# Gator_Environment.net
KiCad netlist of a schematic drawn in EAGLE
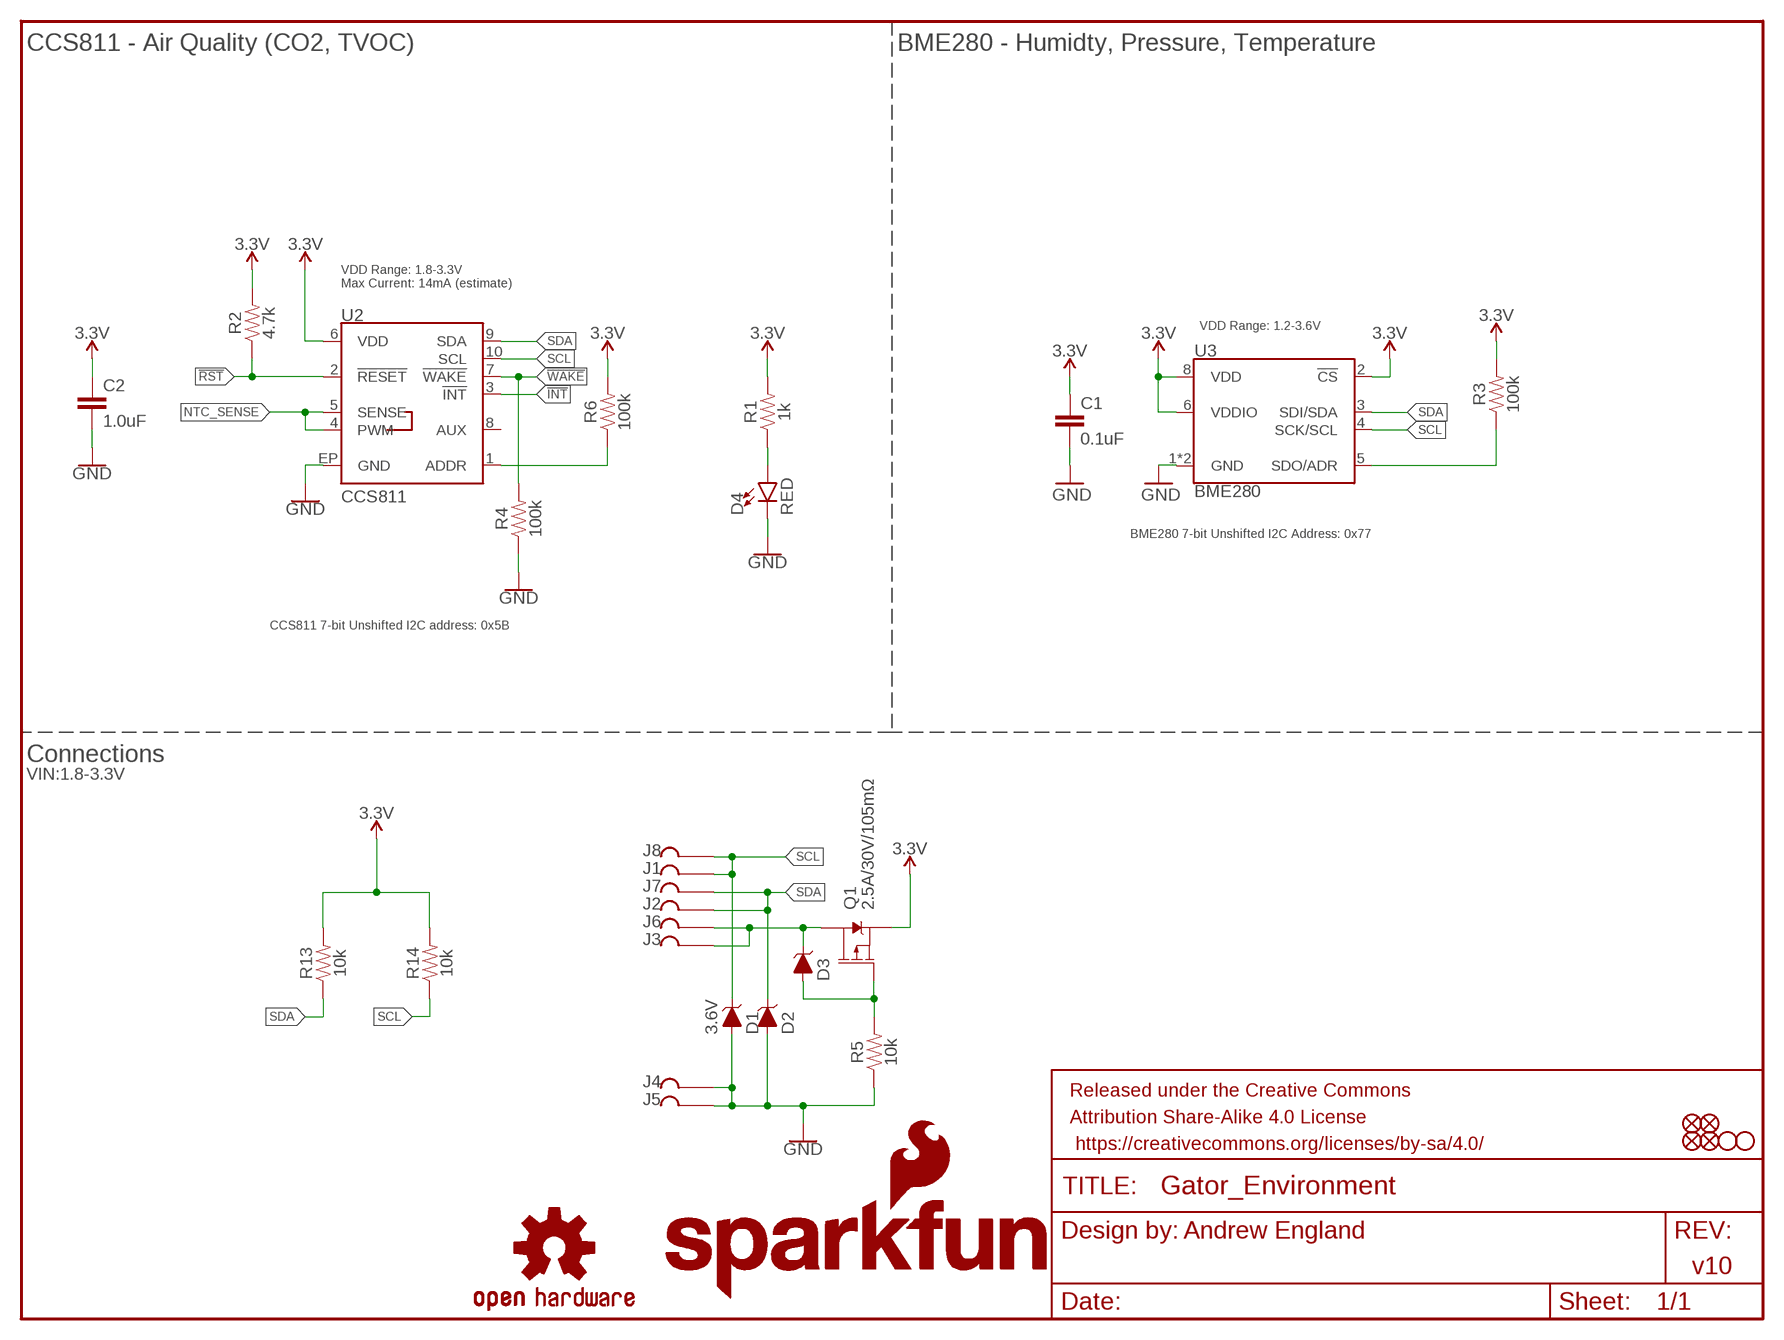
[diagram p0: schematic, sheet 1]

(export (version "E")
  (design (tool "Eeschema 10.0.6"))
  (components
    (comp (ref "C1")
      (value "0.1uF")
      (footprint "eagle-import:0603")
      (libsource (lib "eagle-import") (part "0.1UF-0603-25V-(+80/-20%)"))
    )
    (comp (ref "C2")
      (value "1.0uF")
      (footprint "eagle-import:0603")
      (libsource (lib "eagle-import") (part "1.0UF-0603-16V-10%"))
    )
    (comp (ref "D1")
      (value "3.6V")
      (footprint "eagle-import:SOD-323")
      (libsource (lib "eagle-import") (part "DIODE-ZENER-BZT52C3V6S"))
    )
    (comp (ref "D2")
      (value "3.6V")
      (footprint "eagle-import:SOD-323")
      (libsource (lib "eagle-import") (part "DIODE-ZENER-BZT52C3V6S"))
    )
    (comp (ref "D3")
      (value "3.6V")
      (footprint "eagle-import:SOD-323")
      (libsource (lib "eagle-import") (part "DIODE-ZENER-BZT52C3V6S"))
    )
    (comp (ref "D4")
      (value "RED")
      (footprint "eagle-import:LED-0603")
      (libsource (lib "eagle-import") (part "LED-RED0603"))
    )
    (comp (ref "FD1")
      (value "FIDUCIAL1X2")
      (footprint "eagle-import:FIDUCIAL-1X2")
      (libsource (lib "eagle-import") (part "FIDUCIAL1X2"))
    )
    (comp (ref "FD2")
      (value "FIDUCIAL1X2")
      (footprint "eagle-import:FIDUCIAL-1X2")
      (libsource (lib "eagle-import") (part "FIDUCIAL1X2"))
    )
    (comp (ref "FD3")
      (value "FIDUCIAL1X2")
      (footprint "eagle-import:FIDUCIAL-1X2")
      (libsource (lib "eagle-import") (part "FIDUCIAL1X2"))
    )
    (comp (ref "FD4")
      (value "FIDUCIAL1X2")
      (footprint "eagle-import:FIDUCIAL-1X2")
      (libsource (lib "eagle-import") (part "FIDUCIAL1X2"))
    )
    (comp (ref "FRAME1")
      (value "FRAME-LETTER")
      (footprint "eagle-import:CREATIVE_COMMONS")
      (libsource (lib "eagle-import") (part "FRAME-LETTER"))
    )
    (comp (ref "H2")
      (value "STAND-OFF")
      (footprint "eagle-import:STAND-OFF")
      (libsource (lib "eagle-import") (part "STAND-OFF"))
    )
    (comp (ref "H4")
      (value "STAND-OFF")
      (footprint "eagle-import:STAND-OFF")
      (libsource (lib "eagle-import") (part "STAND-OFF"))
    )
    (comp (ref "J1")
      (value "GATORGATOR_MINI")
      (footprint "eagle-import:GATOR_MINI")
      (libsource (lib "eagle-import") (part "GATORGATOR_MINI"))
    )
    (comp (ref "J2")
      (value "GATORGATOR_MINI")
      (footprint "eagle-import:GATOR_MINI")
      (libsource (lib "eagle-import") (part "GATORGATOR_MINI"))
    )
    (comp (ref "J3")
      (value "GATORGATOR_MINI")
      (footprint "eagle-import:GATOR_MINI")
      (libsource (lib "eagle-import") (part "GATORGATOR_MINI"))
    )
    (comp (ref "J4")
      (value "GATORGATOR_MINI")
      (footprint "eagle-import:GATOR_MINI")
      (libsource (lib "eagle-import") (part "GATORGATOR_MINI"))
    )
    (comp (ref "J5")
      (value "GATORGATOR_MINI")
      (footprint "eagle-import:GATOR_MINI")
      (libsource (lib "eagle-import") (part "GATORGATOR_MINI"))
    )
    (comp (ref "J6")
      (value "GATORGATOR_MINI")
      (footprint "eagle-import:GATOR_MINI")
      (libsource (lib "eagle-import") (part "GATORGATOR_MINI"))
    )
    (comp (ref "J7")
      (value "GATORGATOR_MINI")
      (footprint "eagle-import:GATOR_MINI")
      (libsource (lib "eagle-import") (part "GATORGATOR_MINI"))
    )
    (comp (ref "J8")
      (value "GATORGATOR_MINI")
      (footprint "eagle-import:GATOR_MINI")
      (libsource (lib "eagle-import") (part "GATORGATOR_MINI"))
    )
    (comp (ref "LOGO1")
      (value "SFE_LOGO_NAME.1_INCH")
      (footprint "eagle-import:SFE_LOGO_NAME_.1")
      (libsource (lib "eagle-import") (part "SFE_LOGO_NAME.1_INCH"))
    )
    (comp (ref "LOGO2")
      (value "SFE_LOGO_NAME_FLAME.1_INCH")
      (footprint "eagle-import:SFE_LOGO_NAME_FLAME_.1")
      (libsource (lib "eagle-import") (part "SFE_LOGO_NAME_FLAME.1_INCH"))
    )
    (comp (ref "LOGO4")
      (value "OSHW-LOGOS")
      (footprint "eagle-import:OSHW-LOGO-S")
      (libsource (lib "eagle-import") (part "OSHW-LOGOS"))
    )
    (comp (ref "Q1")
      (value "2.5A/30V/105mΩ")
      (footprint "eagle-import:SOT23-3")
      (libsource (lib "eagle-import") (part "MOSFET_PCH-DMG2307L"))
    )
    (comp (ref "R1")
      (value "1k")
      (footprint "eagle-import:0603")
      (libsource (lib "eagle-import") (part "1KOHM-0603-1/10W-1%"))
    )
    (comp (ref "R2")
      (value "4.7k")
      (footprint "eagle-import:0603")
      (libsource (lib "eagle-import") (part "4.7KOHM-0603-1/10W-1%"))
    )
    (comp (ref "R3")
      (value "100k")
      (footprint "eagle-import:0603")
      (libsource (lib "eagle-import") (part "100KOHM-0603-1/10W-1%"))
    )
    (comp (ref "R4")
      (value "100k")
      (footprint "eagle-import:0603")
      (libsource (lib "eagle-import") (part "100KOHM-0603-1/10W-1%"))
    )
    (comp (ref "R5")
      (value "10k")
      (footprint "eagle-import:0603")
      (libsource (lib "eagle-import") (part "10KOHM-0603-1/10W-1%"))
    )
    (comp (ref "R6")
      (value "100k")
      (footprint "eagle-import:0603")
      (libsource (lib "eagle-import") (part "100KOHM-0603-1/10W-1%"))
    )
    (comp (ref "R13")
      (value "10k")
      (footprint "eagle-import:0603")
      (libsource (lib "eagle-import") (part "10KOHM-0603-1/10W-1%"))
    )
    (comp (ref "R14")
      (value "10k")
      (footprint "eagle-import:0603")
      (libsource (lib "eagle-import") (part "10KOHM-0603-1/10W-1%"))
    )
    (comp (ref "U2")
      (value "CCS811")
      (footprint "eagle-import:LGA10")
      (libsource (lib "eagle-import") (part "CCS811PRODUCTION"))
    )
    (comp (ref "U3")
      (value "BME280")
      (footprint "eagle-import:LGA-8-2.5X2.5")
      (libsource (lib "eagle-import") (part "BME280"))
    )
  )
  (nets
    (net (code "1") (name "/~{INT}") (class "Default")
      (node (ref "U2") (pin "3") (pinfunction "~{INT}_3") (pintype "bidirectional"))
    )
    (net (code "2") (name "/~{RST}") (class "Default")
      (node (ref "R2") (pin "1") (pinfunction "1_1") (pintype "passive"))
      (node (ref "U2") (pin "2") (pinfunction "~{RESET}_2") (pintype "bidirectional"))
    )
    (net (code "3") (name "/~{WAKE}") (class "Default")
      (node (ref "R4") (pin "2") (pinfunction "2_2") (pintype "passive"))
      (node (ref "U2") (pin "7") (pinfunction "~{WAKE}_7") (pintype "bidirectional"))
    )
    (net (code "4") (name "3.3V") (class "Default")
      (node (ref "C1") (pin "1") (pinfunction "1_1") (pintype "passive"))
      (node (ref "C2") (pin "1") (pinfunction "1_1") (pintype "passive"))
      (node (ref "Q1") (pin "2") (pinfunction "S_2") (pintype "bidirectional"))
      (node (ref "R1") (pin "2") (pinfunction "2_2") (pintype "passive"))
      (node (ref "R13") (pin "2") (pinfunction "2_2") (pintype "passive"))
      (node (ref "R14") (pin "2") (pinfunction "2_2") (pintype "passive"))
      (node (ref "R2") (pin "2") (pinfunction "2_2") (pintype "passive"))
      (node (ref "R3") (pin "2") (pinfunction "2_2") (pintype "passive"))
      (node (ref "R6") (pin "2") (pinfunction "2_2") (pintype "passive"))
      (node (ref "U2") (pin "6") (pinfunction "VDD_6") (pintype "bidirectional"))
      (node (ref "U3") (pin "2") (pinfunction "~{CS}_2") (pintype "bidirectional"))
      (node (ref "U3") (pin "6") (pinfunction "VDDIO_6") (pintype "bidirectional"))
      (node (ref "U3") (pin "8") (pinfunction "VDD_8") (pintype "bidirectional"))
    )
    (net (code "5") (name "GND") (class "Default")
      (node (ref "C1") (pin "2") (pinfunction "2_2") (pintype "passive"))
      (node (ref "C2") (pin "2") (pinfunction "2_2") (pintype "passive"))
      (node (ref "D1") (pin "A") (pinfunction "A_A") (pintype "passive"))
      (node (ref "D2") (pin "A") (pinfunction "A_A") (pintype "passive"))
      (node (ref "D4") (pin "C") (pinfunction "C_C") (pintype "passive"))
      (node (ref "J4") (pin "P$2") (pinfunction "P$1_P$2") (pintype "bidirectional"))
      (node (ref "J5") (pin "P$2") (pinfunction "P$1_P$2") (pintype "bidirectional"))
      (node (ref "R4") (pin "1") (pinfunction "1_1") (pintype "passive"))
      (node (ref "R5") (pin "1") (pinfunction "1_1") (pintype "passive"))
      (node (ref "U2") (pin "EP") (pinfunction "GND_EP") (pintype "bidirectional"))
      (node (ref "U3") (pin "1") (pinfunction "GND_1") (pintype "bidirectional"))
      (node (ref "U3") (pin "7") (pinfunction "GND_7") (pintype "bidirectional"))
    )
    (net (code "6") (name "NTC_SENSE") (class "Default")
      (node (ref "U2") (pin "4") (pinfunction "PWM_4") (pintype "bidirectional"))
      (node (ref "U2") (pin "5") (pinfunction "SENSE_5") (pintype "bidirectional"))
    )
    (net (code "7") (name "Net-(D4-PadA)") (class "Default")
      (node (ref "D4") (pin "A") (pinfunction "A_A") (pintype "passive"))
      (node (ref "R1") (pin "1") (pinfunction "1_1") (pintype "passive"))
    )
    (net (code "8") (name "Net-(J3-P$1)") (class "Default")
      (node (ref "D3") (pin "C") (pinfunction "C_C") (pintype "passive"))
      (node (ref "J3") (pin "P$2") (pinfunction "P$1_P$2") (pintype "bidirectional"))
      (node (ref "J6") (pin "P$2") (pinfunction "P$1_P$2") (pintype "bidirectional"))
      (node (ref "Q1") (pin "3") (pinfunction "D_3") (pintype "bidirectional"))
    )
    (net (code "9") (name "Net-(Q1-G)") (class "Default")
      (node (ref "D3") (pin "A") (pinfunction "A_A") (pintype "passive"))
      (node (ref "Q1") (pin "1") (pinfunction "G_1") (pintype "bidirectional"))
      (node (ref "R5") (pin "2") (pinfunction "2_2") (pintype "passive"))
    )
    (net (code "10") (name "Net-(U2-ADDR)") (class "Default")
      (node (ref "R6") (pin "1") (pinfunction "1_1") (pintype "passive"))
      (node (ref "U2") (pin "1") (pinfunction "ADDR_1") (pintype "bidirectional"))
    )
    (net (code "11") (name "Net-(U3-SDO{slash}ADR)") (class "Default")
      (node (ref "R3") (pin "1") (pinfunction "1_1") (pintype "passive"))
      (node (ref "U3") (pin "5") (pinfunction "SDO/ADR_5") (pintype "bidirectional"))
    )
    (net (code "12") (name "SCL") (class "Default")
      (node (ref "D1") (pin "C") (pinfunction "C_C") (pintype "passive"))
      (node (ref "J1") (pin "P$2") (pinfunction "P$1_P$2") (pintype "bidirectional"))
      (node (ref "J8") (pin "P$2") (pinfunction "P$1_P$2") (pintype "bidirectional"))
      (node (ref "R14") (pin "1") (pinfunction "1_1") (pintype "passive"))
      (node (ref "U2") (pin "10") (pinfunction "SCL_10") (pintype "bidirectional"))
      (node (ref "U3") (pin "4") (pinfunction "SCK/SCL_4") (pintype "bidirectional"))
    )
    (net (code "13") (name "SDA") (class "Default")
      (node (ref "D2") (pin "C") (pinfunction "C_C") (pintype "passive"))
      (node (ref "J2") (pin "P$2") (pinfunction "P$1_P$2") (pintype "bidirectional"))
      (node (ref "J7") (pin "P$2") (pinfunction "P$1_P$2") (pintype "bidirectional"))
      (node (ref "R13") (pin "1") (pinfunction "1_1") (pintype "passive"))
      (node (ref "U2") (pin "9") (pinfunction "SDA_9") (pintype "bidirectional"))
      (node (ref "U3") (pin "3") (pinfunction "SDI/SDA_3") (pintype "bidirectional"))
    )
    (net (code "14") (name "unconnected-(U2-AUX-Pad8)") (class "Default")
      (node (ref "U2") (pin "8") (pinfunction "AUX_8") (pintype "bidirectional"))
    )
  )
)
